# LCL_SYM_5V.net
KiCad netlist of a schematic drawn in Altium Designer
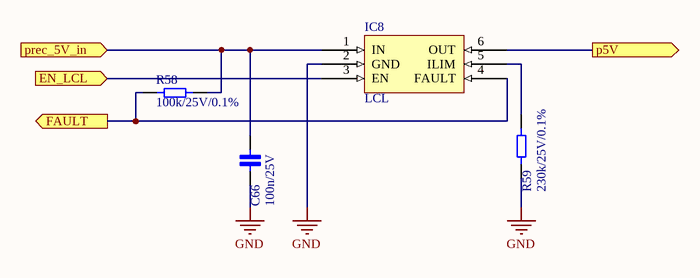
[diagram p0: LCL_SYM_5V.SchDoc]

(export (version "E")
  (design (tool "Eeschema 10.0.6"))
  (components
    (comp (ref "C66")
      (value "100n/25V")
      (footprint "CAP_0603")
      (description "Ceramic Capacitor 100n / 0603 / 25V / ±5%, Wurth Elektronik MLCC")
      (libsource (lib "Cubesat_lib") (part "Cap_0603_100n"))
    )
    (comp (ref "IC8")
      (value "LCL")
      (footprint "SOT-23-6")
      (description "Latch-off Current Limiter")
      (libsource (lib "Cubesat_lib") (part "TPS2553"))
    )
    (comp (ref "R58")
      (value "100k/25V/0.1%")
      (footprint "RES_0603")
      (description "Vishay, thin film resistor 100k/25V/0.1%")
      (libsource (lib "Cubesat_lib") (part "Res_0603_100k"))
    )
    (comp (ref "R59")
      (value "230k/25V/0.1%")
      (footprint "RES_0603")
      (description "Vishay, thin film resistor 230k/25V/0.1%")
      (libsource (lib "Cubesat_lib") (part "Res_0603_230k"))
    )
  )
  (nets
    (net (code "1") (name "/EN_LCL") (class "Default")
      (node (ref "IC8") (pin "3") (pinfunction "EN_3") (pintype "input"))
    )
    (net (code "2") (name "/FAULT") (class "Default")
      (node (ref "IC8") (pin "4") (pinfunction "FAULT_4") (pintype "input"))
      (node (ref "R58") (pin "1") (pinfunction "1_1") (pintype "passive"))
    )
    (net (code "3") (name "/p5V") (class "Default")
      (node (ref "IC8") (pin "6") (pinfunction "OUT_6") (pintype "input"))
    )
    (net (code "4") (name "/prec_5V_in") (class "Default")
      (node (ref "C66") (pin "2") (pinfunction "2_2") (pintype "passive"))
      (node (ref "IC8") (pin "1") (pinfunction "IN_1") (pintype "input"))
      (node (ref "R58") (pin "2") (pinfunction "2_2") (pintype "passive"))
    )
    (net (code "5") (name "GND") (class "Default")
      (node (ref "C66") (pin "1") (pinfunction "1_1") (pintype "passive"))
      (node (ref "IC8") (pin "2") (pinfunction "GND_2") (pintype "input"))
      (node (ref "R59") (pin "2") (pinfunction "2_2") (pintype "passive"))
    )
    (net (code "6") (name "Net-(IC8-ILIM)") (class "Default")
      (node (ref "IC8") (pin "5") (pinfunction "ILIM_5") (pintype "input"))
      (node (ref "R59") (pin "2") (pinfunction "2_2") (pintype "passive"))
    )
  )
)
